# lab3_task1.net
KiCad netlist of a schematic drawn in EAGLE
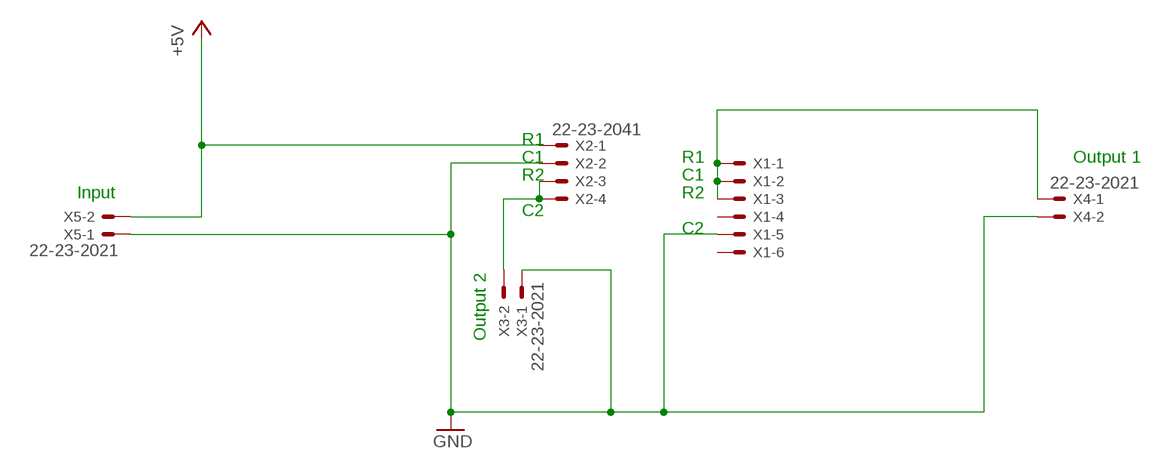
[diagram p0: schematic, sheet 1]

(export (version "E")
  (design (tool "Eeschema 10.0.6"))
  (components
    (comp (ref "X1")
      (value "22-23-2061")
      (footprint "eagle-import:22-23-2061")
      (fields (field (name "MF") "MOLEX"))
      (libsource (lib "eagle-import") (part "22-23-2061"))
    )
    (comp (ref "X2")
      (value "22-23-2041")
      (footprint "eagle-import:22-23-2041")
      (fields (field (name "MF") "MOLEX"))
      (libsource (lib "eagle-import") (part "22-23-2041"))
    )
    (comp (ref "X3")
      (value "22-23-2021")
      (footprint "eagle-import:22-23-2021")
      (fields (field (name "MF") "MOLEX"))
      (libsource (lib "eagle-import") (part "22-23-2021"))
    )
    (comp (ref "X4")
      (value "22-23-2021")
      (footprint "eagle-import:22-23-2021")
      (fields (field (name "MF") "MOLEX"))
      (libsource (lib "eagle-import") (part "22-23-2021"))
    )
    (comp (ref "X5")
      (value "22-23-2021")
      (footprint "eagle-import:22-23-2021")
      (fields (field (name "MF") "MOLEX"))
      (libsource (lib "eagle-import") (part "22-23-2021"))
    )
  )
  (nets
    (net (code "1") (name "+5V") (class "Default")
      (node (ref "X2") (pin "1") (pinfunction "S_1") (pintype "passive"))
      (node (ref "X5") (pin "2") (pinfunction "S_2") (pintype "passive"))
    )
    (net (code "2") (name "GND") (class "Default")
      (node (ref "X1") (pin "5") (pinfunction "S_5") (pintype "passive"))
      (node (ref "X2") (pin "2") (pinfunction "S_2") (pintype "passive"))
      (node (ref "X3") (pin "1") (pinfunction "S_1") (pintype "passive"))
      (node (ref "X4") (pin "2") (pinfunction "S_2") (pintype "passive"))
      (node (ref "X5") (pin "1") (pinfunction "S_1") (pintype "passive"))
    )
    (net (code "3") (name "Net-(X1A-S)") (class "Default")
      (node (ref "X1") (pin "1") (pinfunction "S_1") (pintype "passive"))
      (node (ref "X1") (pin "2") (pinfunction "S_2") (pintype "passive"))
      (node (ref "X1") (pin "3") (pinfunction "S_3") (pintype "passive"))
      (node (ref "X4") (pin "1") (pinfunction "S_1") (pintype "passive"))
    )
    (net (code "4") (name "Net-(X2C-S)") (class "Default")
      (node (ref "X2") (pin "3") (pinfunction "S_3") (pintype "passive"))
      (node (ref "X2") (pin "4") (pinfunction "S_4") (pintype "passive"))
      (node (ref "X3") (pin "2") (pinfunction "S_2") (pintype "passive"))
    )
    (net (code "5") (name "unconnected-(X1D-S-Pad4)") (class "Default")
      (node (ref "X1") (pin "4") (pinfunction "S_4") (pintype "passive"))
    )
    (net (code "6") (name "unconnected-(X1F-S-Pad6)") (class "Default")
      (node (ref "X1") (pin "6") (pinfunction "S_6") (pintype "passive"))
    )
  )
)
